# breakout.net
KiCad netlist of a schematic drawn in EAGLE
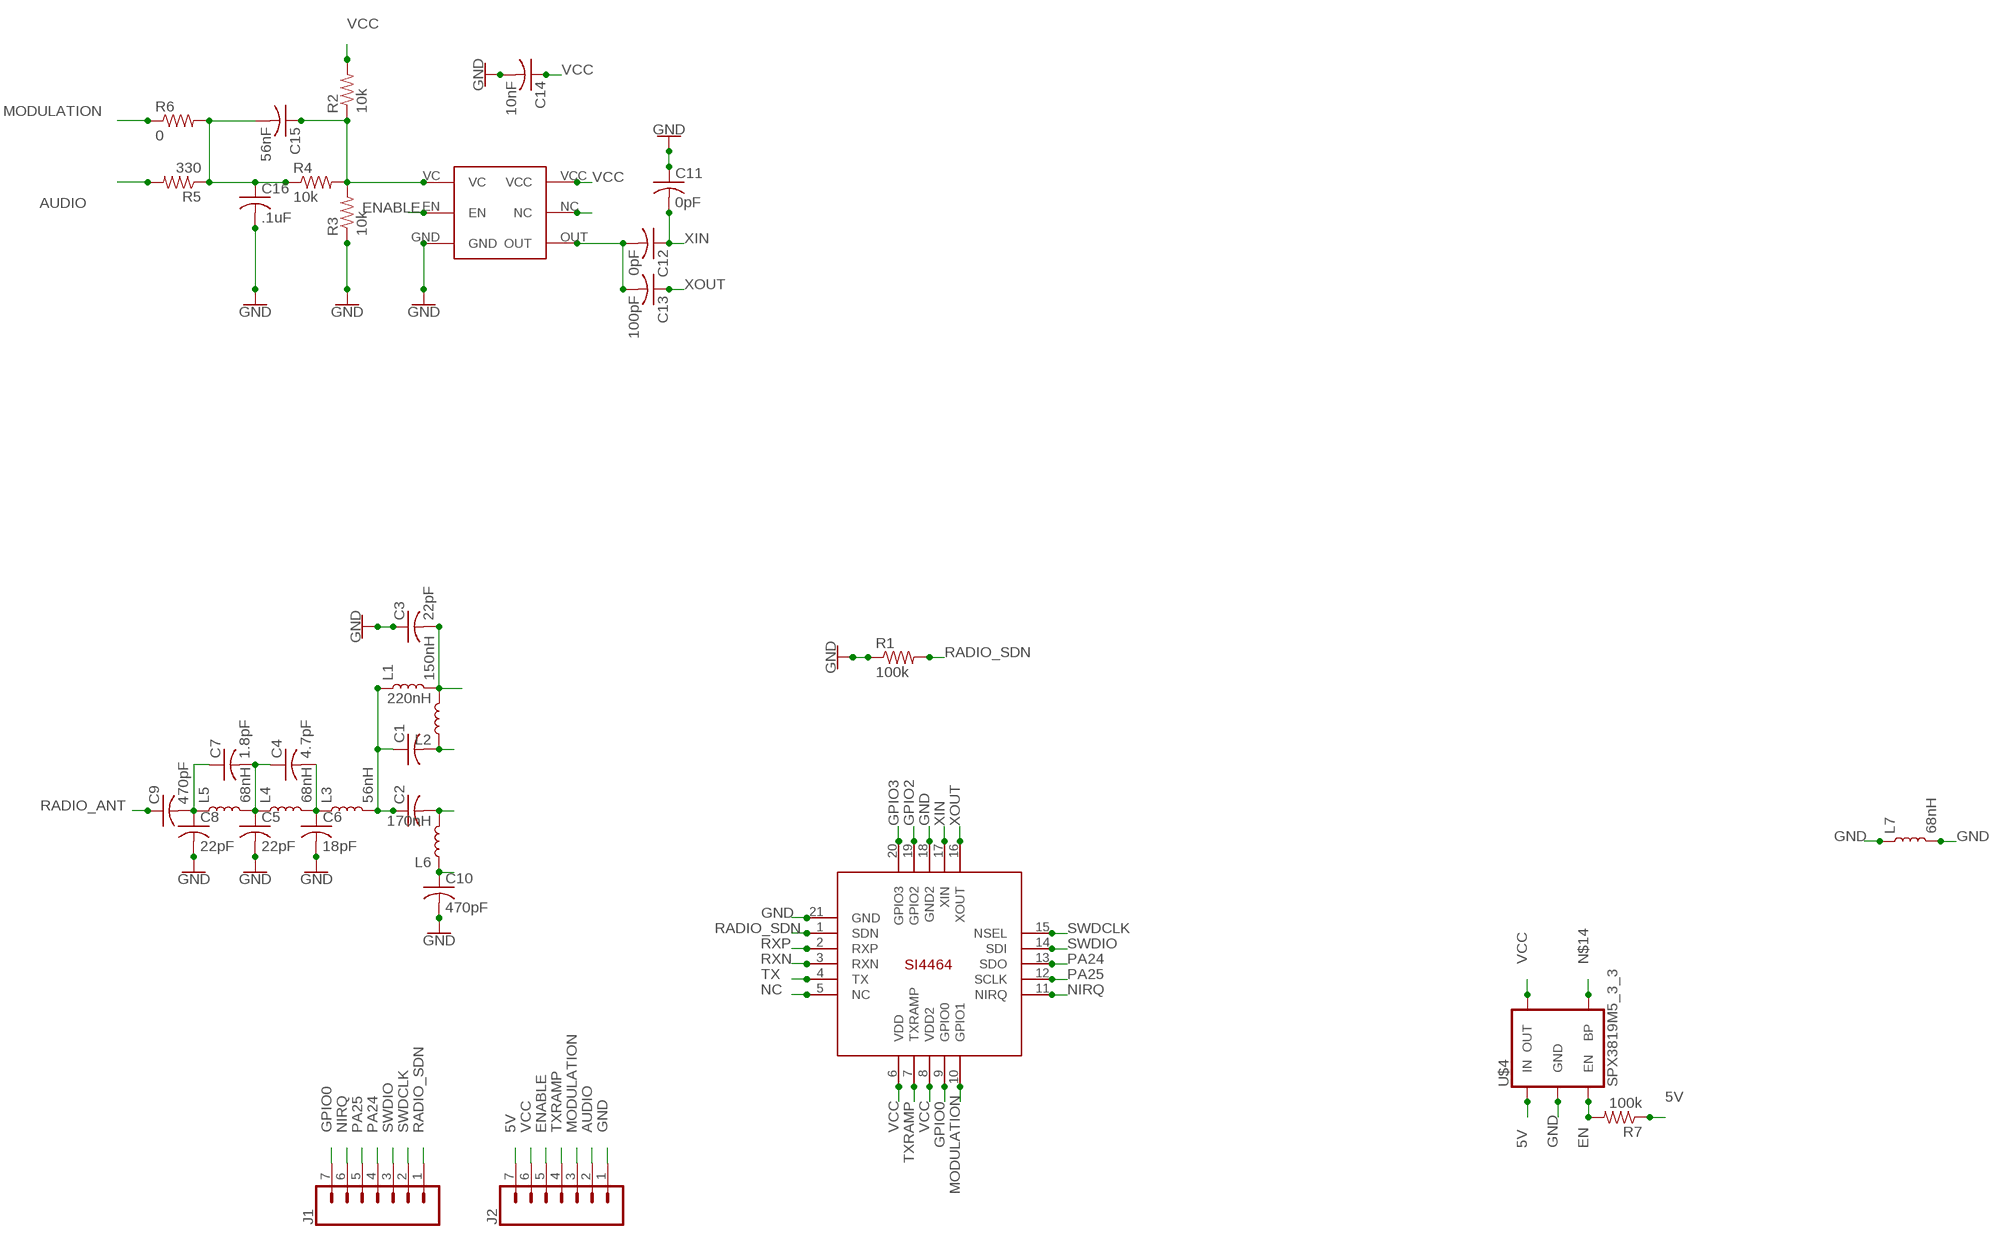
[diagram p0: schematic, sheet 1]

(export (version "E")
  (design (tool "Eeschema 10.0.6"))
  (components
    (comp (ref "C1")
      (value "C-USC0402K")
      (footprint "eagle-import:C0402K")
      (libsource (lib "eagle-import") (part "C-USC0402K"))
    )
    (comp (ref "C2")
      (value "C-USC0402K")
      (footprint "eagle-import:C0402K")
      (libsource (lib "eagle-import") (part "C-USC0402K"))
    )
    (comp (ref "C3")
      (value "22pF")
      (footprint "eagle-import:C0402K")
      (libsource (lib "eagle-import") (part "C-USC0402K"))
    )
    (comp (ref "C4")
      (value "4.7pF")
      (footprint "eagle-import:C0402K")
      (libsource (lib "eagle-import") (part "C-USC0402K"))
    )
    (comp (ref "C5")
      (value "22pF")
      (footprint "eagle-import:C0402K")
      (libsource (lib "eagle-import") (part "C-USC0402K"))
    )
    (comp (ref "C6")
      (value "18pF")
      (footprint "eagle-import:C0402K")
      (libsource (lib "eagle-import") (part "C-USC0402K"))
    )
    (comp (ref "C7")
      (value "1.8pF")
      (footprint "eagle-import:C0402K")
      (libsource (lib "eagle-import") (part "C-USC0402K"))
    )
    (comp (ref "C8")
      (value "22pF")
      (footprint "eagle-import:C0402K")
      (libsource (lib "eagle-import") (part "C-USC0402K"))
    )
    (comp (ref "C9")
      (value "470pF")
      (footprint "eagle-import:C0402K")
      (libsource (lib "eagle-import") (part "C-USC0402K"))
    )
    (comp (ref "C10")
      (value "470pF")
      (footprint "eagle-import:C0402K")
      (libsource (lib "eagle-import") (part "C-USC0402K"))
    )
    (comp (ref "C11")
      (value "0pF")
      (footprint "eagle-import:C0402K")
      (libsource (lib "eagle-import") (part "C-USC0402K"))
    )
    (comp (ref "C12")
      (value "0pF")
      (footprint "eagle-import:C0402K")
      (libsource (lib "eagle-import") (part "C-USC0402K"))
    )
    (comp (ref "C13")
      (value "100pF")
      (footprint "eagle-import:C0402K")
      (libsource (lib "eagle-import") (part "C-USC0402K"))
    )
    (comp (ref "C14")
      (value "10nF")
      (footprint "eagle-import:C0402K")
      (libsource (lib "eagle-import") (part "C-USC0402K"))
    )
    (comp (ref "C15")
      (value "56nF")
      (footprint "eagle-import:C0402K")
      (libsource (lib "eagle-import") (part "C-USC0402K"))
    )
    (comp (ref "C16")
      (value ".1uF")
      (footprint "eagle-import:C0402K")
      (libsource (lib "eagle-import") (part "C-USC0402K"))
    )
    (comp (ref "J1")
      (value "CONN_07")
      (footprint "eagle-import:1X07")
      (libsource (lib "eagle-import") (part "CONN_07"))
    )
    (comp (ref "J2")
      (value "CONN_07")
      (footprint "eagle-import:1X07")
      (libsource (lib "eagle-import") (part "CONN_07"))
    )
    (comp (ref "L1")
      (value "150nH")
      (footprint "eagle-import:0603")
      (libsource (lib "eagle-import") (part "INDUCTOR-0603-33NH"))
    )
    (comp (ref "L2")
      (value "220nH")
      (footprint "eagle-import:0603")
      (libsource (lib "eagle-import") (part "INDUCTOR-0603-33NH"))
    )
    (comp (ref "L3")
      (value "56nH")
      (footprint "eagle-import:0603")
      (libsource (lib "eagle-import") (part "INDUCTOR-0603-33NH"))
    )
    (comp (ref "L4")
      (value "68nH")
      (footprint "eagle-import:0603")
      (libsource (lib "eagle-import") (part "INDUCTOR-0603-33NH"))
    )
    (comp (ref "L5")
      (value "68nH")
      (footprint "eagle-import:0603")
      (libsource (lib "eagle-import") (part "INDUCTOR-0603-33NH"))
    )
    (comp (ref "L6")
      (value "170nH")
      (footprint "eagle-import:0603")
      (libsource (lib "eagle-import") (part "INDUCTOR-0603-33NH"))
    )
    (comp (ref "L7")
      (value "68nH")
      (footprint "eagle-import:0603")
      (libsource (lib "eagle-import") (part "INDUCTOR-0603-33NH"))
    )
    (comp (ref "R1")
      (value "100k")
      (footprint "eagle-import:R0402")
      (libsource (lib "eagle-import") (part "R-US_R0402"))
    )
    (comp (ref "R2")
      (value "10k")
      (footprint "eagle-import:R0402")
      (libsource (lib "eagle-import") (part "R-US_R0402"))
    )
    (comp (ref "R3")
      (value "10k")
      (footprint "eagle-import:R0402")
      (libsource (lib "eagle-import") (part "R-US_R0402"))
    )
    (comp (ref "R4")
      (value "10k")
      (footprint "eagle-import:R0402")
      (libsource (lib "eagle-import") (part "R-US_R0402"))
    )
    (comp (ref "R5")
      (value "330")
      (footprint "eagle-import:R0402")
      (libsource (lib "eagle-import") (part "R-US_R0402"))
    )
    (comp (ref "R6")
      (value "0")
      (footprint "eagle-import:R0402")
      (libsource (lib "eagle-import") (part "R-US_R0402"))
    )
    (comp (ref "R7")
      (value "100k")
      (footprint "eagle-import:R0402")
      (libsource (lib "eagle-import") (part "R-US_R0402"))
    )
    (comp (ref "U$1")
      (value "HC53BR-27")
      (footprint "eagle-import:OSCILLATOR-SMD-7.5X5.2-6PIN")
      (libsource (lib "eagle-import") (part "HC53BR-27"))
    )
    (comp (ref "U$2")
      (value "SI4464")
      (footprint "eagle-import:QFN20+GNDPAD")
      (libsource (lib "eagle-import") (part "SI4464"))
    )
    (comp (ref "U$4")
      (value "SPX3819M5_3_3")
      (footprint "eagle-import:SOT23-5")
      (libsource (lib "eagle-import") (part "V_REG_SPX3819-SOT23-5"))
    )
  )
  (nets
    (net (code "1") (name "/5V") (class "Default")
      (node (ref "J2") (pin "7") (pinfunction "7_7") (pintype "passive"))
      (node (ref "R7") (pin "1") (pinfunction "1_1") (pintype "passive"))
      (node (ref "U$4") (pin "1") (pinfunction "IN_1") (pintype "input"))
    )
    (net (code "2") (name "/AUDIO") (class "Default")
      (node (ref "J2") (pin "2") (pinfunction "2_2") (pintype "passive"))
      (node (ref "R5") (pin "2") (pinfunction "2_2") (pintype "passive"))
    )
    (net (code "3") (name "/EN") (class "Default")
      (node (ref "R7") (pin "2") (pinfunction "2_2") (pintype "passive"))
      (node (ref "U$4") (pin "3") (pinfunction "EN_3") (pintype "input"))
    )
    (net (code "4") (name "/ENABLE") (class "Default")
      (node (ref "J2") (pin "5") (pinfunction "5_5") (pintype "passive"))
      (node (ref "U$1") (pin "EN") (pinfunction "EN_EN") (pintype "bidirectional"))
    )
    (net (code "5") (name "/GPIO0") (class "Default")
      (node (ref "J1") (pin "7") (pinfunction "7_7") (pintype "passive"))
      (node (ref "U$2") (pin "9") (pinfunction "GPIO0_9") (pintype "bidirectional"))
    )
    (net (code "6") (name "/GPIO2") (class "Default")
      (node (ref "U$2") (pin "19") (pinfunction "GPIO2_19") (pintype "bidirectional"))
    )
    (net (code "7") (name "/GPIO3") (class "Default")
      (node (ref "U$2") (pin "20") (pinfunction "GPIO3_20") (pintype "bidirectional"))
    )
    (net (code "8") (name "/MODULATION") (class "Default")
      (node (ref "J2") (pin "3") (pinfunction "3_3") (pintype "passive"))
      (node (ref "R6") (pin "1") (pinfunction "1_1") (pintype "passive"))
      (node (ref "U$2") (pin "10") (pinfunction "GPIO1_10") (pintype "bidirectional"))
    )
    (net (code "9") (name "/N$14") (class "Default")
      (node (ref "U$4") (pin "4") (pinfunction "BP_4") (pintype "input"))
    )
    (net (code "10") (name "/NC") (class "Default")
      (node (ref "U$2") (pin "5") (pinfunction "NC _5") (pintype "bidirectional"))
    )
    (net (code "11") (name "/NIRQ") (class "Default")
      (node (ref "J1") (pin "6") (pinfunction "6_6") (pintype "passive"))
      (node (ref "U$2") (pin "11") (pinfunction "NIRQ_11") (pintype "bidirectional"))
    )
    (net (code "12") (name "/PA24") (class "Default")
      (node (ref "J1") (pin "4") (pinfunction "4_4") (pintype "passive"))
      (node (ref "U$2") (pin "13") (pinfunction "SDO_13") (pintype "bidirectional"))
    )
    (net (code "13") (name "/PA25") (class "Default")
      (node (ref "J1") (pin "5") (pinfunction "5_5") (pintype "passive"))
      (node (ref "U$2") (pin "12") (pinfunction "SCLK_12") (pintype "bidirectional"))
    )
    (net (code "14") (name "/RADIO_ANT") (class "Default")
      (node (ref "C9") (pin "1") (pinfunction "1_1") (pintype "passive"))
    )
    (net (code "15") (name "/RADIO_SDN") (class "Default")
      (node (ref "J1") (pin "1") (pinfunction "1_1") (pintype "passive"))
      (node (ref "R1") (pin "2") (pinfunction "2_2") (pintype "passive"))
      (node (ref "U$2") (pin "1") (pinfunction "SDN_1") (pintype "bidirectional"))
    )
    (net (code "16") (name "/RXN") (class "Default")
      (node (ref "C1") (pin "2") (pinfunction "2_2") (pintype "passive"))
      (node (ref "L2") (pin "1") (pinfunction "1_1") (pintype "passive"))
      (node (ref "U$2") (pin "3") (pinfunction "RXN_3") (pintype "bidirectional"))
    )
    (net (code "17") (name "/RXP") (class "Default")
      (node (ref "C3") (pin "2") (pinfunction "2_2") (pintype "passive"))
      (node (ref "L1") (pin "2") (pinfunction "2_2") (pintype "passive"))
      (node (ref "L2") (pin "2") (pinfunction "2_2") (pintype "passive"))
      (node (ref "U$2") (pin "2") (pinfunction "RXP_2") (pintype "bidirectional"))
    )
    (net (code "18") (name "/SWDCLK") (class "Default")
      (node (ref "J1") (pin "2") (pinfunction "2_2") (pintype "passive"))
      (node (ref "U$2") (pin "15") (pinfunction "NSEL_15") (pintype "bidirectional"))
    )
    (net (code "19") (name "/SWDIO") (class "Default")
      (node (ref "J1") (pin "3") (pinfunction "3_3") (pintype "passive"))
      (node (ref "U$2") (pin "14") (pinfunction "SDI_14") (pintype "bidirectional"))
    )
    (net (code "20") (name "/TX") (class "Default")
      (node (ref "C2") (pin "2") (pinfunction "2_2") (pintype "passive"))
      (node (ref "L6") (pin "2") (pinfunction "2_2") (pintype "passive"))
      (node (ref "U$2") (pin "4") (pinfunction "TX_4") (pintype "bidirectional"))
    )
    (net (code "21") (name "/TXRAMP") (class "Default")
      (node (ref "J2") (pin "4") (pinfunction "4_4") (pintype "passive"))
      (node (ref "U$2") (pin "7") (pinfunction "TXRAMP_7") (pintype "bidirectional"))
    )
    (net (code "22") (name "/VCC") (class "Default")
      (node (ref "C10") (pin "1") (pinfunction "1_1") (pintype "passive"))
      (node (ref "C14") (pin "1") (pinfunction "1_1") (pintype "passive"))
      (node (ref "J2") (pin "6") (pinfunction "6_6") (pintype "passive"))
      (node (ref "L6") (pin "1") (pinfunction "1_1") (pintype "passive"))
      (node (ref "R2") (pin "2") (pinfunction "2_2") (pintype "passive"))
      (node (ref "U$1") (pin "VCC") (pinfunction "VCC_VCC") (pintype "bidirectional"))
      (node (ref "U$2") (pin "6") (pinfunction "VDD_6") (pintype "bidirectional"))
      (node (ref "U$2") (pin "8") (pinfunction "VDD2_8") (pintype "bidirectional"))
      (node (ref "U$4") (pin "5") (pinfunction "OUT_5") (pintype "passive"))
    )
    (net (code "23") (name "/XIN") (class "Default")
      (node (ref "C11") (pin "2") (pinfunction "2_2") (pintype "passive"))
      (node (ref "C12") (pin "1") (pinfunction "1_1") (pintype "passive"))
      (node (ref "U$2") (pin "17") (pinfunction "XIN_17") (pintype "bidirectional"))
    )
    (net (code "24") (name "/XOUT") (class "Default")
      (node (ref "C13") (pin "1") (pinfunction "1_1") (pintype "passive"))
      (node (ref "U$2") (pin "16") (pinfunction "XOUT_16") (pintype "bidirectional"))
    )
    (net (code "25") (name "GND") (class "Default")
      (node (ref "C10") (pin "2") (pinfunction "2_2") (pintype "passive"))
      (node (ref "C11") (pin "1") (pinfunction "1_1") (pintype "passive"))
      (node (ref "C14") (pin "2") (pinfunction "2_2") (pintype "passive"))
      (node (ref "C16") (pin "2") (pinfunction "2_2") (pintype "passive"))
      (node (ref "C3") (pin "1") (pinfunction "1_1") (pintype "passive"))
      (node (ref "C5") (pin "2") (pinfunction "2_2") (pintype "passive"))
      (node (ref "C6") (pin "2") (pinfunction "2_2") (pintype "passive"))
      (node (ref "C8") (pin "2") (pinfunction "2_2") (pintype "passive"))
      (node (ref "J2") (pin "1") (pinfunction "1_1") (pintype "passive"))
      (node (ref "L7") (pin "1") (pinfunction "1_1") (pintype "passive"))
      (node (ref "L7") (pin "2") (pinfunction "2_2") (pintype "passive"))
      (node (ref "R1") (pin "1") (pinfunction "1_1") (pintype "passive"))
      (node (ref "R3") (pin "1") (pinfunction "1_1") (pintype "passive"))
      (node (ref "U$1") (pin "GND") (pinfunction "GND_GND") (pintype "bidirectional"))
      (node (ref "U$2") (pin "18") (pinfunction "GND2_18") (pintype "bidirectional"))
      (node (ref "U$2") (pin "21") (pinfunction "GND_21") (pintype "bidirectional"))
      (node (ref "U$4") (pin "2") (pinfunction "GND_2") (pintype "input"))
    )
    (net (code "26") (name "Net-(C1-Pad1)") (class "Default")
      (node (ref "C1") (pin "1") (pinfunction "1_1") (pintype "passive"))
      (node (ref "C2") (pin "1") (pinfunction "1_1") (pintype "passive"))
      (node (ref "L1") (pin "1") (pinfunction "1_1") (pintype "passive"))
      (node (ref "L3") (pin "2") (pinfunction "2_2") (pintype "passive"))
    )
    (net (code "27") (name "Net-(C4-Pad1)") (class "Default")
      (node (ref "C4") (pin "1") (pinfunction "1_1") (pintype "passive"))
      (node (ref "C5") (pin "1") (pinfunction "1_1") (pintype "passive"))
      (node (ref "C7") (pin "2") (pinfunction "2_2") (pintype "passive"))
      (node (ref "L4") (pin "1") (pinfunction "1_1") (pintype "passive"))
      (node (ref "L5") (pin "2") (pinfunction "2_2") (pintype "passive"))
    )
    (net (code "28") (name "Net-(C4-Pad2)") (class "Default")
      (node (ref "C4") (pin "2") (pinfunction "2_2") (pintype "passive"))
      (node (ref "C6") (pin "1") (pinfunction "1_1") (pintype "passive"))
      (node (ref "L3") (pin "1") (pinfunction "1_1") (pintype "passive"))
      (node (ref "L4") (pin "2") (pinfunction "2_2") (pintype "passive"))
    )
    (net (code "29") (name "Net-(C7-Pad1)") (class "Default")
      (node (ref "C7") (pin "1") (pinfunction "1_1") (pintype "passive"))
      (node (ref "C8") (pin "1") (pinfunction "1_1") (pintype "passive"))
      (node (ref "C9") (pin "2") (pinfunction "2_2") (pintype "passive"))
      (node (ref "L5") (pin "1") (pinfunction "1_1") (pintype "passive"))
    )
    (net (code "30") (name "Net-(C12-Pad2)") (class "Default")
      (node (ref "C12") (pin "2") (pinfunction "2_2") (pintype "passive"))
      (node (ref "C13") (pin "2") (pinfunction "2_2") (pintype "passive"))
      (node (ref "U$1") (pin "OUT") (pinfunction "OUT_OUT") (pintype "bidirectional"))
    )
    (net (code "31") (name "Net-(C15-Pad1)") (class "Default")
      (node (ref "C15") (pin "1") (pinfunction "1_1") (pintype "passive"))
      (node (ref "R2") (pin "1") (pinfunction "1_1") (pintype "passive"))
      (node (ref "R3") (pin "2") (pinfunction "2_2") (pintype "passive"))
      (node (ref "R4") (pin "2") (pinfunction "2_2") (pintype "passive"))
      (node (ref "U$1") (pin "VC") (pinfunction "VC_VC") (pintype "bidirectional"))
    )
    (net (code "32") (name "Net-(C15-Pad2)") (class "Default")
      (node (ref "C15") (pin "2") (pinfunction "2_2") (pintype "passive"))
      (node (ref "C16") (pin "1") (pinfunction "1_1") (pintype "passive"))
      (node (ref "R4") (pin "1") (pinfunction "1_1") (pintype "passive"))
      (node (ref "R5") (pin "1") (pinfunction "1_1") (pintype "passive"))
      (node (ref "R6") (pin "2") (pinfunction "2_2") (pintype "passive"))
    )
    (net (code "33") (name "unconnected-(U$1-PadNC)") (class "Default")
      (node (ref "U$1") (pin "NC") (pinfunction "NC_NC") (pintype "bidirectional"))
    )
  )
)
